# STM32MP25XXAK_Power.net
KiCad netlist of a schematic drawn in Altium Designer
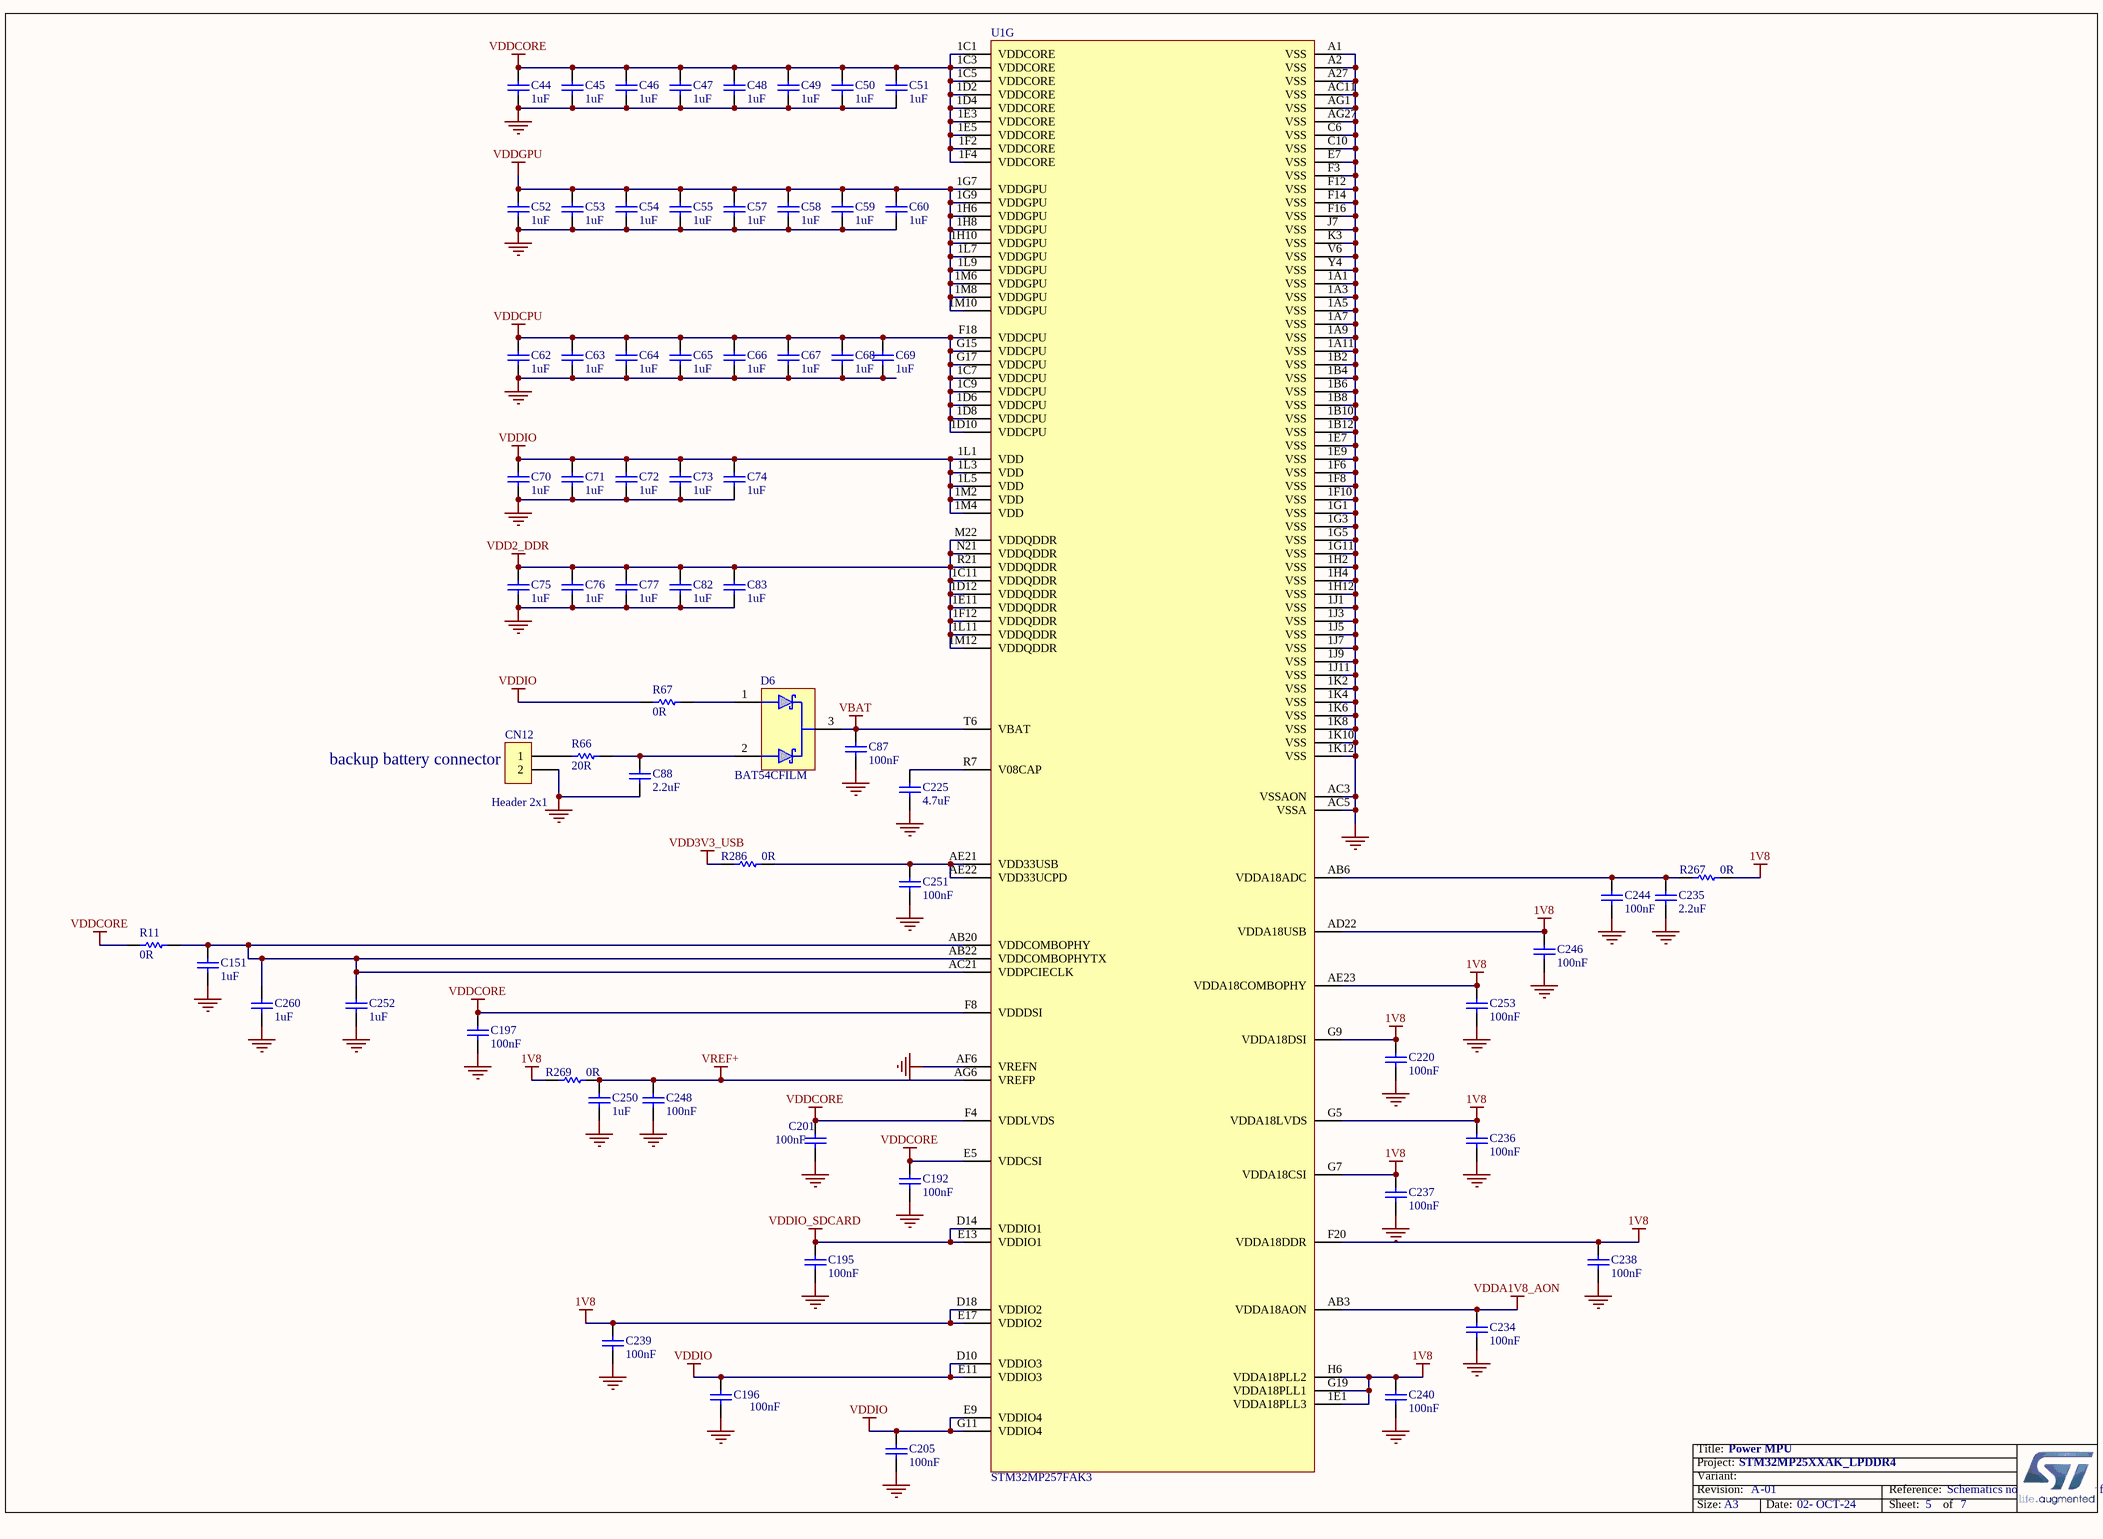
[diagram p0: STM32MP25XXAK Power.SchDoc]

(export (version "E")
  (design (tool "Eeschema 10.0.6"))
  (components
    (comp (ref "C44")
      (value "1uF")
      (footprint "C0201_MURATA_GRM033_H0P3")
      (description "Capacitor, MLCC, 1uF, 6.3V, X5R, +/-20%, 0201, T=0,3mm")
      (fields (field (name "INTERNAL_PART_NUMBER") "MCD-02377") (field (name "MANUFACTURER") "MURATA"))
      (libsource (lib "MCD_PARTS_database") (part "Capacitor"))
    )
    (comp (ref "C45")
      (value "1uF")
      (footprint "C0201_MURATA_GRM033_H0P3")
      (description "Capacitor, MLCC, 1uF, 6.3V, X5R, +/-20%, 0201, T=0,3mm")
      (fields (field (name "INTERNAL_PART_NUMBER") "MCD-02377") (field (name "MANUFACTURER") "MURATA"))
      (libsource (lib "MCD_PARTS_database") (part "Capacitor"))
    )
    (comp (ref "C46")
      (value "1uF")
      (footprint "C0201_MURATA_GRM033_H0P3")
      (description "Capacitor, MLCC, 1uF, 6.3V, X5R, +/-20%, 0201, T=0,3mm")
      (fields (field (name "INTERNAL_PART_NUMBER") "MCD-02377") (field (name "MANUFACTURER") "MURATA"))
      (libsource (lib "MCD_PARTS_database") (part "Capacitor"))
    )
    (comp (ref "C47")
      (value "1uF")
      (footprint "C0201_MURATA_GRM033_H0P3")
      (description "Capacitor, MLCC, 1uF, 6.3V, X5R, +/-20%, 0201, T=0,3mm")
      (fields (field (name "INTERNAL_PART_NUMBER") "MCD-02377") (field (name "MANUFACTURER") "MURATA"))
      (libsource (lib "MCD_PARTS_database") (part "Capacitor"))
    )
    (comp (ref "C48")
      (value "1uF")
      (footprint "C0201_MURATA_GRM033_H0P3")
      (description "Capacitor, MLCC, 1uF, 6.3V, X5R, +/-20%, 0201, T=0,3mm")
      (fields (field (name "INTERNAL_PART_NUMBER") "MCD-02377") (field (name "MANUFACTURER") "MURATA"))
      (libsource (lib "MCD_PARTS_database") (part "Capacitor"))
    )
    (comp (ref "C49")
      (value "1uF")
      (footprint "C0201_MURATA_GRM033_H0P3")
      (description "Capacitor, MLCC, 1uF, 6.3V, X5R, +/-20%, 0201, T=0,3mm")
      (fields (field (name "INTERNAL_PART_NUMBER") "MCD-02377") (field (name "MANUFACTURER") "MURATA"))
      (libsource (lib "MCD_PARTS_database") (part "Capacitor"))
    )
    (comp (ref "C50")
      (value "1uF")
      (footprint "C0201_MURATA_GRM033_H0P3")
      (description "Capacitor, MLCC, 1uF, 6.3V, X5R, +/-20%, 0201, T=0,3mm")
      (fields (field (name "INTERNAL_PART_NUMBER") "MCD-02377") (field (name "MANUFACTURER") "MURATA"))
      (libsource (lib "MCD_PARTS_database") (part "Capacitor"))
    )
    (comp (ref "C51")
      (value "1uF")
      (footprint "C0201_MURATA_GRM033_H0P3")
      (description "Capacitor, MLCC, 1uF, 6.3V, X5R, +/-20%, 0201, T=0,3mm")
      (fields (field (name "INTERNAL_PART_NUMBER") "MCD-02377") (field (name "MANUFACTURER") "MURATA"))
      (libsource (lib "MCD_PARTS_database") (part "Capacitor"))
    )
    (comp (ref "C52")
      (value "1uF")
      (footprint "C0201_MURATA_GRM033_H0P3")
      (description "Capacitor, MLCC, 1uF, 6.3V, X5R, +/-20%, 0201, T=0,3mm")
      (fields (field (name "INTERNAL_PART_NUMBER") "MCD-02377") (field (name "MANUFACTURER") "MURATA"))
      (libsource (lib "MCD_PARTS_database") (part "Capacitor"))
    )
    (comp (ref "C53")
      (value "1uF")
      (footprint "C0201_MURATA_GRM033_H0P3")
      (description "Capacitor, MLCC, 1uF, 6.3V, X5R, +/-20%, 0201, T=0,3mm")
      (fields (field (name "INTERNAL_PART_NUMBER") "MCD-02377") (field (name "MANUFACTURER") "MURATA"))
      (libsource (lib "MCD_PARTS_database") (part "Capacitor"))
    )
    (comp (ref "C54")
      (value "1uF")
      (footprint "C0201_MURATA_GRM033_H0P3")
      (description "Capacitor, MLCC, 1uF, 6.3V, X5R, +/-20%, 0201, T=0,3mm")
      (fields (field (name "INTERNAL_PART_NUMBER") "MCD-02377") (field (name "MANUFACTURER") "MURATA"))
      (libsource (lib "MCD_PARTS_database") (part "Capacitor"))
    )
    (comp (ref "C55")
      (value "1uF")
      (footprint "C0201_MURATA_GRM033_H0P3")
      (description "Capacitor, MLCC, 1uF, 6.3V, X5R, +/-20%, 0201, T=0,3mm")
      (fields (field (name "INTERNAL_PART_NUMBER") "MCD-02377") (field (name "MANUFACTURER") "MURATA"))
      (libsource (lib "MCD_PARTS_database") (part "Capacitor"))
    )
    (comp (ref "C57")
      (value "1uF")
      (footprint "C0201_MURATA_GRM033_H0P3")
      (description "Capacitor, MLCC, 1uF, 6.3V, X5R, +/-20%, 0201, T=0,3mm")
      (fields (field (name "INTERNAL_PART_NUMBER") "MCD-02377") (field (name "MANUFACTURER") "MURATA"))
      (libsource (lib "MCD_PARTS_database") (part "Capacitor"))
    )
    (comp (ref "C58")
      (value "1uF")
      (footprint "C0201_MURATA_GRM033_H0P3")
      (description "Capacitor, MLCC, 1uF, 6.3V, X5R, +/-20%, 0201, T=0,3mm")
      (fields (field (name "INTERNAL_PART_NUMBER") "MCD-02377") (field (name "MANUFACTURER") "MURATA"))
      (libsource (lib "MCD_PARTS_database") (part "Capacitor"))
    )
    (comp (ref "C59")
      (value "1uF")
      (footprint "C0201_MURATA_GRM033_H0P3")
      (description "Capacitor, MLCC, 1uF, 6.3V, X5R, +/-20%, 0201, T=0,3mm")
      (fields (field (name "INTERNAL_PART_NUMBER") "MCD-02377") (field (name "MANUFACTURER") "MURATA"))
      (libsource (lib "MCD_PARTS_database") (part "Capacitor"))
    )
    (comp (ref "C60")
      (value "1uF")
      (footprint "C0201_MURATA_GRM033_H0P3")
      (description "Capacitor, MLCC, 1uF, 6.3V, X5R, +/-20%, 0201, T=0,3mm")
      (fields (field (name "INTERNAL_PART_NUMBER") "MCD-02377") (field (name "MANUFACTURER") "MURATA"))
      (libsource (lib "MCD_PARTS_database") (part "Capacitor"))
    )
    (comp (ref "C62")
      (value "1uF")
      (footprint "C0201_MURATA_GRM033_H0P3")
      (description "Capacitor, MLCC, 1uF, 6.3V, X5R, +/-20%, 0201, T=0,3mm")
      (fields (field (name "INTERNAL_PART_NUMBER") "MCD-02377") (field (name "MANUFACTURER") "MURATA"))
      (libsource (lib "MCD_PARTS_database") (part "Capacitor"))
    )
    (comp (ref "C63")
      (value "1uF")
      (footprint "C0201_MURATA_GRM033_H0P3")
      (description "Capacitor, MLCC, 1uF, 6.3V, X5R, +/-20%, 0201, T=0,3mm")
      (fields (field (name "INTERNAL_PART_NUMBER") "MCD-02377") (field (name "MANUFACTURER") "MURATA"))
      (libsource (lib "MCD_PARTS_database") (part "Capacitor"))
    )
    (comp (ref "C64")
      (value "1uF")
      (footprint "C0201_MURATA_GRM033_H0P3")
      (description "Capacitor, MLCC, 1uF, 6.3V, X5R, +/-20%, 0201, T=0,3mm")
      (fields (field (name "INTERNAL_PART_NUMBER") "MCD-02377") (field (name "MANUFACTURER") "MURATA"))
      (libsource (lib "MCD_PARTS_database") (part "Capacitor"))
    )
    (comp (ref "C65")
      (value "1uF")
      (footprint "C0201_MURATA_GRM033_H0P3")
      (description "Capacitor, MLCC, 1uF, 6.3V, X5R, +/-20%, 0201, T=0,3mm")
      (fields (field (name "INTERNAL_PART_NUMBER") "MCD-02377") (field (name "MANUFACTURER") "MURATA"))
      (libsource (lib "MCD_PARTS_database") (part "Capacitor"))
    )
    (comp (ref "C66")
      (value "1uF")
      (footprint "C0201_MURATA_GRM033_H0P3")
      (description "Capacitor, MLCC, 1uF, 6.3V, X5R, +/-20%, 0201, T=0,3mm")
      (fields (field (name "INTERNAL_PART_NUMBER") "MCD-02377") (field (name "MANUFACTURER") "MURATA"))
      (libsource (lib "MCD_PARTS_database") (part "Capacitor"))
    )
    (comp (ref "C67")
      (value "1uF")
      (footprint "C0201_MURATA_GRM033_H0P3")
      (description "Capacitor, MLCC, 1uF, 6.3V, X5R, +/-20%, 0201, T=0,3mm")
      (fields (field (name "INTERNAL_PART_NUMBER") "MCD-02377") (field (name "MANUFACTURER") "MURATA"))
      (libsource (lib "MCD_PARTS_database") (part "Capacitor"))
    )
    (comp (ref "C68")
      (value "1uF")
      (footprint "C0201_MURATA_GRM033_H0P3")
      (description "Capacitor, MLCC, 1uF, 6.3V, X5R, +/-20%, 0201, T=0,3mm")
      (fields (field (name "INTERNAL_PART_NUMBER") "MCD-02377") (field (name "MANUFACTURER") "MURATA"))
      (libsource (lib "MCD_PARTS_database") (part "Capacitor"))
    )
    (comp (ref "C69")
      (value "1uF")
      (footprint "C0201_MURATA_GRM033_H0P3")
      (description "Capacitor, MLCC, 1uF, 6.3V, X5R, +/-20%, 0201, T=0,3mm")
      (fields (field (name "INTERNAL_PART_NUMBER") "MCD-02377") (field (name "MANUFACTURER") "MURATA"))
      (libsource (lib "MCD_PARTS_database") (part "Capacitor"))
    )
    (comp (ref "C70")
      (value "1uF")
      (footprint "C0201_MURATA_GRM033_H0P3")
      (description "Capacitor, MLCC, 1uF, 6.3V, X5R, +/-20%, 0201, T=0,3mm")
      (fields (field (name "INTERNAL_PART_NUMBER") "MCD-02377") (field (name "MANUFACTURER") "MURATA"))
      (libsource (lib "MCD_PARTS_database") (part "Capacitor"))
    )
    (comp (ref "C71")
      (value "1uF")
      (footprint "C0201_MURATA_GRM033_H0P3")
      (description "Capacitor, MLCC, 1uF, 6.3V, X5R, +/-20%, 0201, T=0,3mm")
      (fields (field (name "INTERNAL_PART_NUMBER") "MCD-02377") (field (name "MANUFACTURER") "MURATA"))
      (libsource (lib "MCD_PARTS_database") (part "Capacitor"))
    )
    (comp (ref "C72")
      (value "1uF")
      (footprint "C0201_MURATA_GRM033_H0P3")
      (description "Capacitor, MLCC, 1uF, 6.3V, X5R, +/-20%, 0201, T=0,3mm")
      (fields (field (name "INTERNAL_PART_NUMBER") "MCD-02377") (field (name "MANUFACTURER") "MURATA"))
      (libsource (lib "MCD_PARTS_database") (part "Capacitor"))
    )
    (comp (ref "C73")
      (value "1uF")
      (footprint "C0201_MURATA_GRM033_H0P3")
      (description "Capacitor, MLCC, 1uF, 6.3V, X5R, +/-20%, 0201, T=0,3mm")
      (fields (field (name "INTERNAL_PART_NUMBER") "MCD-02377") (field (name "MANUFACTURER") "MURATA"))
      (libsource (lib "MCD_PARTS_database") (part "Capacitor"))
    )
    (comp (ref "C74")
      (value "1uF")
      (footprint "C0201_MURATA_GRM033_H0P3")
      (description "Capacitor, MLCC, 1uF, 6.3V, X5R, +/-20%, 0201, T=0,3mm")
      (fields (field (name "INTERNAL_PART_NUMBER") "MCD-02377") (field (name "MANUFACTURER") "MURATA"))
      (libsource (lib "MCD_PARTS_database") (part "Capacitor"))
    )
    (comp (ref "C75")
      (value "1uF")
      (footprint "C0201_MURATA_GRM033_H0P3")
      (description "Capacitor, MLCC, 1uF, 6.3V, X5R, +/-20%, 0201, T=0,3mm")
      (fields (field (name "INTERNAL_PART_NUMBER") "MCD-02377") (field (name "MANUFACTURER") "MURATA"))
      (libsource (lib "MCD_PARTS_database") (part "Capacitor"))
    )
    (comp (ref "C76")
      (value "1uF")
      (footprint "C0201_MURATA_GRM033_H0P3")
      (description "Capacitor, MLCC, 1uF, 6.3V, X5R, +/-20%, 0201, T=0,3mm")
      (fields (field (name "INTERNAL_PART_NUMBER") "MCD-02377") (field (name "MANUFACTURER") "MURATA"))
      (libsource (lib "MCD_PARTS_database") (part "Capacitor"))
    )
    (comp (ref "C77")
      (value "1uF")
      (footprint "C0201_MURATA_GRM033_H0P3")
      (description "Capacitor, MLCC, 1uF, 6.3V, X5R, +/-20%, 0201, T=0,3mm")
      (fields (field (name "INTERNAL_PART_NUMBER") "MCD-02377") (field (name "MANUFACTURER") "MURATA"))
      (libsource (lib "MCD_PARTS_database") (part "Capacitor"))
    )
    (comp (ref "C82")
      (value "1uF")
      (footprint "C0201_MURATA_GRM033_H0P3")
      (description "Capacitor, MLCC, 1uF, 6.3V, X5R, +/-20%, 0201, T=0,3mm")
      (fields (field (name "INTERNAL_PART_NUMBER") "MCD-02377") (field (name "MANUFACTURER") "MURATA"))
      (libsource (lib "MCD_PARTS_database") (part "Capacitor"))
    )
    (comp (ref "C83")
      (value "1uF")
      (footprint "C0201_MURATA_GRM033_H0P3")
      (description "Capacitor, MLCC, 1uF, 6.3V, X5R, +/-20%, 0201, T=0,3mm")
      (fields (field (name "INTERNAL_PART_NUMBER") "MCD-02377") (field (name "MANUFACTURER") "MURATA"))
      (libsource (lib "MCD_PARTS_database") (part "Capacitor"))
    )
    (comp (ref "C87")
      (value "100nF")
      (footprint "C0402")
      (description "Capacitor,100nF,16V,X7R,10%,0402")
      (fields
        (field (name "INTERNAL_PART_NUMBER") "MCD-00006")
        (field (name "MANUFACTURER_PART_NUMBER") "CC0402KRX7R7BB104")
        (field (name "PROVIDED_BY") "SUBCO")
      )
      (libsource (lib "MCD_PARTS_database") (part "Capacitor"))
    )
    (comp (ref "C88")
      (value "2.2uF")
      (footprint "C0402")
      (description "Capacitor, MLCC, 2.2uF, 6V3, X5R,+/-10%, 0402, T=0.5mm")
      (fields (field (name "INTERNAL_PART_NUMBER") "MCD-01823") (field (name "MANUFACTURER") "MURATA"))
      (libsource (lib "MCD_PARTS_database") (part "Capacitor"))
    )
    (comp (ref "C151")
      (value "1uF")
      (footprint "C0201_MURATA_GRM033_H0P3")
      (description "Capacitor, MLCC, 1uF, 6.3V, X5R, +/-20%, 0201, T=0,3mm")
      (fields
        (field (name "INTERNAL_PART_NUMBER") "MCD-02377")
        (field (name "MANUFACTURER_PART_NUMBER") "GRM033R60J105MEA2")
      )
      (libsource (lib "MCD_PARTS_database") (part "Capacitor"))
    )
    (comp (ref "C192")
      (value "100nF")
      (footprint "C0201_MURATA_GRM033_H0P3")
      (description "Capacitor, MLCC,100nF, 10V, X7R, +/-10%, 0201, T=0.3mm")
      (fields (field (name "INTERNAL_PART_NUMBER") "MCD-01535") (field (name "MANUFACTURER") "MURATA"))
      (libsource (lib "MCD_PARTS_database") (part "Capacitor"))
    )
    (comp (ref "C195")
      (value "100nF")
      (footprint "C0201_MURATA_GRM033_H0P3")
      (description "Capacitor, MLCC,100nF, 10V, X7R, +/-10%, 0201, T=0.3mm")
      (fields (field (name "INTERNAL_PART_NUMBER") "MCD-01535") (field (name "MANUFACTURER") "MURATA"))
      (libsource (lib "MCD_PARTS_database") (part "Capacitor"))
    )
    (comp (ref "C196")
      (value "100nF")
      (footprint "C0201_MURATA_GRM033_H0P3")
      (description "Capacitor, MLCC,100nF, 10V, X7R, +/-10%, 0201, T=0.3mm")
      (fields (field (name "INTERNAL_PART_NUMBER") "MCD-01535") (field (name "MANUFACTURER") "MURATA"))
      (libsource (lib "MCD_PARTS_database") (part "Capacitor"))
    )
    (comp (ref "C197")
      (value "100nF")
      (footprint "C0201_MURATA_GRM033_H0P3")
      (description "Capacitor, MLCC,100nF, 10V, X7R, +/-10%, 0201, T=0.3mm")
      (fields (field (name "INTERNAL_PART_NUMBER") "MCD-01535") (field (name "MANUFACTURER") "MURATA"))
      (libsource (lib "MCD_PARTS_database") (part "Capacitor"))
    )
    (comp (ref "C201")
      (value "100nF")
      (footprint "C0201_MURATA_GRM033_H0P3")
      (description "Capacitor, MLCC,100nF, 10V, X7R, +/-10%, 0201, T=0.3mm")
      (fields (field (name "INTERNAL_PART_NUMBER") "MCD-01535") (field (name "MANUFACTURER") "MURATA"))
      (libsource (lib "MCD_PARTS_database") (part "Capacitor"))
    )
    (comp (ref "C205")
      (value "100nF")
      (footprint "C0201_MURATA_GRM033_H0P3")
      (description "Capacitor, MLCC,100nF, 10V, X7R, +/-10%, 0201, T=0.3mm")
      (fields (field (name "INTERNAL_PART_NUMBER") "MCD-01535") (field (name "MANUFACTURER") "MURATA"))
      (libsource (lib "MCD_PARTS_database") (part "Capacitor"))
    )
    (comp (ref "C220")
      (value "100nF")
      (footprint "C0201_MURATA_GRM033_H0P3")
      (description "Capacitor, MLCC,100nF, 10V, X7R, +/-10%, 0201, T=0.3mm")
      (fields (field (name "INTERNAL_PART_NUMBER") "MCD-01535") (field (name "MANUFACTURER") "MURATA"))
      (libsource (lib "MCD_PARTS_database") (part "Capacitor"))
    )
    (comp (ref "C225")
      (value "4.7uF")
      (footprint "C0201_H0P5")
      (description "Capacitor, MLCC, 4,7uF, 6V3, X5R, +/-20%, 0201, T=0.5mm")
      (fields (field (name "INTERNAL_PART_NUMBER") "MCD-01534") (field (name "MANUFACTURER") "MURATA"))
      (libsource (lib "MCD_PARTS_database") (part "Capacitor"))
    )
    (comp (ref "C234")
      (value "100nF")
      (footprint "C0201_MURATA_GRM033_H0P3")
      (description "Capacitor, MLCC,100nF, 10V, X7R, +/-10%, 0201, T=0.3mm")
      (fields (field (name "INTERNAL_PART_NUMBER") "MCD-01535") (field (name "MANUFACTURER") "MURATA"))
      (libsource (lib "MCD_PARTS_database") (part "Capacitor"))
    )
    (comp (ref "C235")
      (value "2.2uF")
      (footprint "C0201_H0P5")
      (description "Capacitor, MLCC, 2.2uF, 10V, X5R,+/-10%, 0201, T=0.5mm")
      (fields (field (name "INTERNAL_PART_NUMBER") "MCD-02235") (field (name "MANUFACTURER") "MURATA"))
      (libsource (lib "MCD_PARTS_database") (part "Capacitor"))
    )
    (comp (ref "C236")
      (value "100nF")
      (footprint "C0201_MURATA_GRM033_H0P3")
      (description "Capacitor, MLCC,100nF, 10V, X7R, +/-10%, 0201, T=0.3mm")
      (fields (field (name "INTERNAL_PART_NUMBER") "MCD-01535") (field (name "MANUFACTURER") "MURATA"))
      (libsource (lib "MCD_PARTS_database") (part "Capacitor"))
    )
    (comp (ref "C237")
      (value "100nF")
      (footprint "C0201_MURATA_GRM033_H0P3")
      (description "Capacitor, MLCC,100nF, 10V, X7R, +/-10%, 0201, T=0.3mm")
      (fields (field (name "INTERNAL_PART_NUMBER") "MCD-01535") (field (name "MANUFACTURER") "MURATA"))
      (libsource (lib "MCD_PARTS_database") (part "Capacitor"))
    )
    (comp (ref "C238")
      (value "100nF")
      (footprint "C0201_MURATA_GRM033_H0P3")
      (description "Capacitor, MLCC,100nF, 10V, X7R, +/-10%, 0201, T=0.3mm")
      (fields (field (name "INTERNAL_PART_NUMBER") "MCD-01535") (field (name "MANUFACTURER") "MURATA"))
      (libsource (lib "MCD_PARTS_database") (part "Capacitor"))
    )
    (comp (ref "C239")
      (value "100nF")
      (footprint "C0201_MURATA_GRM033_H0P3")
      (description "Capacitor, MLCC,100nF, 10V, X7R, +/-10%, 0201, T=0.3mm")
      (fields (field (name "INTERNAL_PART_NUMBER") "MCD-01535") (field (name "MANUFACTURER") "MURATA"))
      (libsource (lib "MCD_PARTS_database") (part "Capacitor"))
    )
    (comp (ref "C240")
      (value "100nF")
      (footprint "C0201_MURATA_GRM033_H0P3")
      (description "Capacitor, MLCC,100nF, 10V, X7R, +/-10%, 0201, T=0.3mm")
      (fields (field (name "INTERNAL_PART_NUMBER") "MCD-01535") (field (name "MANUFACTURER") "MURATA"))
      (libsource (lib "MCD_PARTS_database") (part "Capacitor"))
    )
    (comp (ref "C244")
      (value "100nF")
      (footprint "C0201_MURATA_GRM033_H0P3")
      (description "Capacitor, MLCC,100nF, 10V, X7R, +/-10%, 0201, T=0.3mm")
      (fields (field (name "INTERNAL_PART_NUMBER") "MCD-01535") (field (name "MANUFACTURER") "MURATA"))
      (libsource (lib "MCD_PARTS_database") (part "Capacitor"))
    )
    (comp (ref "C246")
      (value "100nF")
      (footprint "C0201_MURATA_GRM033_H0P3")
      (description "Capacitor, MLCC,100nF, 10V, X7R, +/-10%, 0201, T=0.3mm")
      (fields (field (name "INTERNAL_PART_NUMBER") "MCD-01535") (field (name "MANUFACTURER") "MURATA"))
      (libsource (lib "MCD_PARTS_database") (part "Capacitor"))
    )
    (comp (ref "C248")
      (value "100nF")
      (footprint "C0201_MURATA_GRM033_H0P3")
      (description "Capacitor, MLCC,100nF, 10V, X7R, +/-10%, 0201, T=0.3mm")
      (fields (field (name "INTERNAL_PART_NUMBER") "MCD-01535") (field (name "MANUFACTURER") "MURATA"))
      (libsource (lib "MCD_PARTS_database") (part "Capacitor"))
    )
    (comp (ref "C250")
      (value "1uF")
      (footprint "C0201_MURATA_GRM033_H0P3")
      (description "Capacitor, MLCC, 1uF, 6.3V, X5R, +/-20%, 0201, T=0,3mm")
      (fields
        (field (name "INTERNAL_PART_NUMBER") "MCD-02377")
        (field (name "MANUFACTURER_PART_NUMBER") "GRM033R60J105MEA2")
      )
      (libsource (lib "MCD_PARTS_database") (part "Capacitor"))
    )
    (comp (ref "C251")
      (value "100nF")
      (footprint "C0201_MURATA_GRM033_H0P3")
      (description "Capacitor, MLCC,100nF, 10V, X7R, +/-10%, 0201, T=0.3mm")
      (fields (field (name "INTERNAL_PART_NUMBER") "MCD-01535") (field (name "MANUFACTURER") "MURATA"))
      (libsource (lib "MCD_PARTS_database") (part "Capacitor"))
    )
    (comp (ref "C252")
      (value "1uF")
      (footprint "C0201_MURATA_GRM033_H0P3")
      (description "Capacitor, MLCC, 1uF, 6.3V, X5R, +/-20%, 0201, T=0,3mm")
      (fields
        (field (name "INTERNAL_PART_NUMBER") "MCD-02377")
        (field (name "MANUFACTURER_PART_NUMBER") "GRM033R60J105MEA2")
      )
      (libsource (lib "MCD_PARTS_database") (part "Capacitor"))
    )
    (comp (ref "C253")
      (value "100nF")
      (footprint "C0201_MURATA_GRM033_H0P3")
      (description "Capacitor, MLCC,100nF, 10V, X7R, +/-10%, 0201, T=0.3mm")
      (fields (field (name "INTERNAL_PART_NUMBER") "MCD-01535") (field (name "MANUFACTURER") "MURATA"))
      (libsource (lib "MCD_PARTS_database") (part "Capacitor"))
    )
    (comp (ref "C260")
      (value "1uF")
      (footprint "C0201_MURATA_GRM033_H0P3")
      (description "Capacitor, MLCC, 1uF, 6.3V, X5R, +/-20%, 0201, T=0,3mm")
      (fields
        (field (name "INTERNAL_PART_NUMBER") "MCD-02377")
        (field (name "MANUFACTURER_PART_NUMBER") "GRM033R60J105MEA2")
      )
      (libsource (lib "MCD_PARTS_database") (part "Capacitor"))
    )
    (comp (ref "CN12")
      (value "Header 2x1")
      (footprint "CON_MOLEX_53047-0210")
      (description "Header 2 circuits, 1.25mm Pitch ,  Vertical, with Friction Lock")
      (fields
        (field (name "INTERNAL_PART_NUMBER") "MCD-00655")
        (field (name "MANUFACTURER_PART_NUMBER") "53047-0210")
        (field (name "PROVIDED_BY") "SUBCO")
      )
      (libsource (lib "MCD_PARTS_database") (part "Header 2x1"))
    )
    (comp (ref "D6")
      (value "BAT54CFILM")
      (footprint "DIO_SOT23")
      (description "Diode, Schottky, Dual Common Cathode, 0V3, 300mA, 40V, SOT-23")
      (fields
        (field (name "INTERNAL_PART_NUMBER") "MCD-03280")
        (field (name "MANUFACTURER") "STMICROELECTRONICS")
      )
      (libsource (lib "MCD_PARTS_database") (part "DIODE_3P_DUAL_COMMON_CATHODE"))
    )
    (comp (ref "R11")
      (value "0R")
      (footprint "R0603")
      (description "Resistor, 0R, 0603, +/-5%, 1/10W")
      (fields (field (name "INTERNAL_PART_NUMBER") "MCD-00056") (field (name "MANUFACTURER") "YAGEO"))
      (libsource (lib "MCD_PARTS_database") (part "Resistor"))
    )
    (comp (ref "R66")
      (value "20R")
      (footprint "R0402")
      (description "Resistor, 20R, 0402, +/-1%, 1/16W")
      (fields (field (name "INTERNAL_PART_NUMBER") "MCD-00058") (field (name "BMS_PART_NUMBER") "9131027"))
      (libsource (lib "MCD_PARTS_database") (part "Resistor"))
    )
    (comp (ref "R67")
      (value "0R")
      (footprint "R0402")
      (description "Resistor, 0R, 0402, +/-5%, 1/16W")
      (fields
        (field (name "INTERNAL_PART_NUMBER") "MCD-00052")
        (field (name "MANUFACTURER_PART_NUMBER") "RC0402JR-070RL")
      )
      (libsource (lib "MCD_PARTS_database") (part "Resistor"))
    )
    (comp (ref "R267")
      (value "0R")
      (footprint "R0402")
      (description "Resistor,0R,0402,5%,1/16W")
      (fields
        (field (name "INTERNAL_PART_NUMBER") "MCD-00052")
        (field (name "MANUFACTURER_PART_NUMBER") "RC0402JR-070RL")
        (field (name "PROVIDED_BY") "SUBCO")
      )
      (libsource (lib "MCD_PARTS_database") (part "Resistor"))
    )
    (comp (ref "R269")
      (value "0R")
      (footprint "R0402")
      (description "Resistor,0R,0402,5%,1/16W")
      (fields
        (field (name "INTERNAL_PART_NUMBER") "MCD-00052")
        (field (name "MANUFACTURER_PART_NUMBER") "RC0402JR-070RL")
        (field (name "PROVIDED_BY") "SUBCO")
      )
      (libsource (lib "MCD_PARTS_database") (part "Resistor"))
    )
    (comp (ref "R286")
      (value "0R")
      (footprint "R0402")
      (description "Resistor,0R,0402,5%,1/16W")
      (fields
        (field (name "INTERNAL_PART_NUMBER") "MCD-00052")
        (field (name "MANUFACTURER_PART_NUMBER") "RC0402JR-070RL")
        (field (name "PROVIDED_BY") "SUBCO")
      )
      (libsource (lib "MCD_PARTS_database") (part "Resistor"))
    )
    (comp (ref "U1")
      (value "STM32MP257FAK3")
      (footprint "ICC_TFBGA424_14X14_P050_H1P20_CODE-B0A2")
      (description "MPU , 2xCortex-A35@1.5GHz, Cortex-M33@400MHz, TFBGA 14x14, pitch 0.5, 808 KB SRAM, With Crypto")
      (fields
        (field (name "INTERNAL_PART_NUMBER") "MCD-03375")
        (field (name "MANUFACTURER") "STMICROELECTRONICS")
      )
      (libsource (lib "MCD_PARTS_database") (part "STM32MP257FAK3"))
    )
  )
  (nets
    (net (code "1") (name "1V8") (class "Default")
      (node (ref "C220") (pin "2") (pinfunction "2_2") (pintype "passive"))
      (node (ref "C236") (pin "2") (pinfunction "2_2") (pintype "passive"))
      (node (ref "C237") (pin "2") (pinfunction "2_2") (pintype "passive"))
      (node (ref "C238") (pin "2") (pinfunction "2_2") (pintype "passive"))
      (node (ref "C239") (pin "2") (pinfunction "2_2") (pintype "passive"))
      (node (ref "C240") (pin "2") (pinfunction "2_2") (pintype "passive"))
      (node (ref "C246") (pin "2") (pinfunction "2_2") (pintype "passive"))
      (node (ref "C253") (pin "2") (pinfunction "2_2") (pintype "passive"))
      (node (ref "R267") (pin "2") (pinfunction "2_2") (pintype "passive"))
      (node (ref "R269") (pin "1") (pinfunction "1_1") (pintype "passive"))
      (node (ref "U1") (pin "1E1") (pinfunction "VDDA18PLL3_1E1") (pintype "passive"))
      (node (ref "U1") (pin "AD22") (pinfunction "VDDA18USB_AD22") (pintype "passive"))
      (node (ref "U1") (pin "AE23") (pinfunction "VDDA18COMBOPHY_AE23") (pintype "passive"))
      (node (ref "U1") (pin "D18") (pinfunction "VDDIO2_D18") (pintype "passive"))
      (node (ref "U1") (pin "E17") (pinfunction "VDDIO2_E17") (pintype "passive"))
      (node (ref "U1") (pin "F20") (pinfunction "VDDA18DDR_F20") (pintype "passive"))
      (node (ref "U1") (pin "G19") (pinfunction "VDDA18PLL1_G19") (pintype "passive"))
      (node (ref "U1") (pin "G5") (pinfunction "VDDA18LVDS_G5") (pintype "passive"))
      (node (ref "U1") (pin "G7") (pinfunction "VDDA18CSI_G7") (pintype "passive"))
      (node (ref "U1") (pin "G9") (pinfunction "VDDA18DSI_G9") (pintype "passive"))
      (node (ref "U1") (pin "H6") (pinfunction "VDDA18PLL2_H6") (pintype "passive"))
    )
    (net (code "2") (name "GND") (class "Default")
      (node (ref "C151") (pin "1") (pinfunction "1_1") (pintype "passive"))
      (node (ref "C192") (pin "1") (pinfunction "1_1") (pintype "passive"))
      (node (ref "C195") (pin "1") (pinfunction "1_1") (pintype "passive"))
      (node (ref "C196") (pin "1") (pinfunction "1_1") (pintype "passive"))
      (node (ref "C197") (pin "1") (pinfunction "1_1") (pintype "passive"))
      (node (ref "C201") (pin "1") (pinfunction "1_1") (pintype "passive"))
      (node (ref "C205") (pin "1") (pinfunction "1_1") (pintype "passive"))
      (node (ref "C220") (pin "1") (pinfunction "1_1") (pintype "passive"))
      (node (ref "C225") (pin "1") (pinfunction "1_1") (pintype "passive"))
      (node (ref "C234") (pin "1") (pinfunction "1_1") (pintype "passive"))
      (node (ref "C235") (pin "1") (pinfunction "1_1") (pintype "passive"))
      (node (ref "C236") (pin "1") (pinfunction "1_1") (pintype "passive"))
      (node (ref "C237") (pin "1") (pinfunction "1_1") (pintype "passive"))
      (node (ref "C238") (pin "1") (pinfunction "1_1") (pintype "passive"))
      (node (ref "C239") (pin "1") (pinfunction "1_1") (pintype "passive"))
      (node (ref "C240") (pin "1") (pinfunction "1_1") (pintype "passive"))
      (node (ref "C244") (pin "1") (pinfunction "1_1") (pintype "passive"))
      (node (ref "C246") (pin "1") (pinfunction "1_1") (pintype "passive"))
      (node (ref "C248") (pin "1") (pinfunction "1_1") (pintype "passive"))
      (node (ref "C250") (pin "1") (pinfunction "1_1") (pintype "passive"))
      (node (ref "C251") (pin "1") (pinfunction "1_1") (pintype "passive"))
      (node (ref "C252") (pin "1") (pinfunction "1_1") (pintype "passive"))
      (node (ref "C253") (pin "1") (pinfunction "1_1") (pintype "passive"))
      (node (ref "C260") (pin "1") (pinfunction "1_1") (pintype "passive"))
      (node (ref "C44") (pin "2") (pinfunction "2_2") (pintype "passive"))
      (node (ref "C45") (pin "1") (pinfunction "1_1") (pintype "passive"))
      (node (ref "C46") (pin "1") (pinfunction "1_1") (pintype "passive"))
      (node (ref "C47") (pin "2") (pinfunction "2_2") (pintype "passive"))
      (node (ref "C48") (pin "1") (pinfunction "1_1") (pintype "passive"))
      (node (ref "C49") (pin "1") (pinfunction "1_1") (pintype "passive"))
      (node (ref "C50") (pin "1") (pinfunction "1_1") (pintype "passive"))
      (node (ref "C51") (pin "1") (pinfunction "1_1") (pintype "passive"))
      (node (ref "C52") (pin "1") (pinfunction "1_1") (pintype "passive"))
      (node (ref "C53") (pin "1") (pinfunction "1_1") (pintype "passive"))
      (node (ref "C54") (pin "1") (pinfunction "1_1") (pintype "passive"))
      (node (ref "C55") (pin "1") (pinfunction "1_1") (pintype "passive"))
      (node (ref "C57") (pin "1") (pinfunction "1_1") (pintype "passive"))
      (node (ref "C58") (pin "1") (pinfunction "1_1") (pintype "passive"))
      (node (ref "C59") (pin "1") (pinfunction "1_1") (pintype "passive"))
      (node (ref "C60") (pin "1") (pinfunction "1_1") (pintype "passive"))
      (node (ref "C62") (pin "2") (pinfunction "2_2") (pintype "passive"))
      (node (ref "C63") (pin "1") (pinfunction "1_1") (pintype "passive"))
      (node (ref "C64") (pin "1") (pinfunction "1_1") (pintype "passive"))
      (node (ref "C65") (pin "2") (pinfunction "2_2") (pintype "passive"))
      (node (ref "C66") (pin "1") (pinfunction "1_1") (pintype "passive"))
      (node (ref "C67") (pin "1") (pinfunction "1_1") (pintype "passive"))
      (node (ref "C68") (pin "1") (pinfunction "1_1") (pintype "passive"))
      (node (ref "C69") (pin "1") (pinfunction "1_1") (pintype "passive"))
      (node (ref "C70") (pin "2") (pinfunction "2_2") (pintype "passive"))
      (node (ref "C71") (pin "1") (pinfunction "1_1") (pintype "passive"))
      (node (ref "C72") (pin "1") (pinfunction "1_1") (pintype "passive"))
      (node (ref "C73") (pin "2") (pinfunction "2_2") (pintype "passive"))
      (node (ref "C74") (pin "1") (pinfunction "1_1") (pintype "passive"))
      (node (ref "C75") (pin "1") (pinfunction "1_1") (pintype "passive"))
      (node (ref "C76") (pin "1") (pinfunction "1_1") (pintype "passive"))
      (node (ref "C77") (pin "2") (pinfunction "2_2") (pintype "passive"))
      (node (ref "C82") (pin "1") (pinfunction "1_1") (pintype "passive"))
      (node (ref "C83") (pin "1") (pinfunction "1_1") (pintype "passive"))
      (node (ref "C87") (pin "1") (pinfunction "1_1") (pintype "passive"))
      (node (ref "C88") (pin "1") (pinfunction "1_1") (pintype "passive"))
      (node (ref "CN12") (pin "2") (pinfunction "2_2") (pintype "passive"))
      (node (ref "U1") (pin "1A1") (pinfunction "VSS_1A1") (pintype "passive"))
      (node (ref "U1") (pin "1A11") (pinfunction "VSS_1A11") (pintype "passive"))
      (node (ref "U1") (pin "1A3") (pinfunction "VSS_1A3") (pintype "passive"))
      (node (ref "U1") (pin "1A5") (pinfunction "VSS_1A5") (pintype "passive"))
      (node (ref "U1") (pin "1A7") (pinfunction "VSS_1A7") (pintype "passive"))
      (node (ref "U1") (pin "1A9") (pinfunction "VSS_1A9") (pintype "passive"))
      (node (ref "U1") (pin "1B10") (pinfunction "VSS_1B10") (pintype "passive"))
      (node (ref "U1") (pin "1B12") (pinfunction "VSS_1B12") (pintype "passive"))
      (node (ref "U1") (pin "1B2") (pinfunction "VSS_1B2") (pintype "passive"))
      (node (ref "U1") (pin "1B4") (pinfunction "VSS_1B4") (pintype "passive"))
      (node (ref "U1") (pin "1B6") (pinfunction "VSS_1B6") (pintype "passive"))
      (node (ref "U1") (pin "1B8") (pinfunction "VSS_1B8") (pintype "passive"))
      (node (ref "U1") (pin "1E7") (pinfunction "VSS_1E7") (pintype "passive"))
      (node (ref "U1") (pin "1E9") (pinfunction "VSS_1E9") (pintype "passive"))
      (node (ref "U1") (pin "1F10") (pinfunction "VSS_1F10") (pintype "passive"))
      (node (ref "U1") (pin "1F6") (pinfunction "VSS_1F6") (pintype "passive"))
      (node (ref "U1") (pin "1F8") (pinfunction "VSS_1F8") (pintype "passive"))
      (node (ref "U1") (pin "1G1") (pinfunction "VSS_1G1") (pintype "passive"))
      (node (ref "U1") (pin "1G11") (pinfunction "VSS_1G11") (pintype "passive"))
      (node (ref "U1") (pin "1G3") (pinfunction "VSS_1G3") (pintype "passive"))
      (node (ref "U1") (pin "1G5") (pinfunction "VSS_1G5") (pintype "passive"))
      (node (ref "U1") (pin "1H12") (pinfunction "VSS_1H12") (pintype "passive"))
      (node (ref "U1") (pin "1H2") (pinfunction "VSS_1H2") (pintype "passive"))
      (node (ref "U1") (pin "1H4") (pinfunction "VSS_1H4") (pintype "passive"))
      (node (ref "U1") (pin "1J1") (pinfunction "VSS_1J1") (pintype "passive"))
      (node (ref "U1") (pin "1J11") (pinfunction "VSS_1J11") (pintype "passive"))
      (node (ref "U1") (pin "1J3") (pinfunction "VSS_1J3") (pintype "passive"))
      (node (ref "U1") (pin "1J5") (pinfunction "VSS_1J5") (pintype "passive"))
      (node (ref "U1") (pin "1J7") (pinfunction "VSS_1J7") (pintype "passive"))
      (node (ref "U1") (pin "1J9") (pinfunction "VSS_1J9") (pintype "passive"))
      (node (ref "U1") (pin "1K10") (pinfunction "VSS_1K10") (pintype "passive"))
      (node (ref "U1") (pin "1K12") (pinfunction "VSS_1K12") (pintype "passive"))
      (node (ref "U1") (pin "1K2") (pinfunction "VSS_1K2") (pintype "passive"))
      (node (ref "U1") (pin "1K4") (pinfunction "VSS_1K4") (pintype "passive"))
      (node (ref "U1") (pin "1K6") (pinfunction "VSS_1K6") (pintype "passive"))
      (node (ref "U1") (pin "1K8") (pinfunction "VSS_1K8") (pintype "passive"))
      (node (ref "U1") (pin "A1") (pinfunction "VSS_A1") (pintype "passive"))
      (node (ref "U1") (pin "A2") (pinfunction "VSS_A2") (pintype "passive"))
      (node (ref "U1") (pin "A27") (pinfunction "VSS_A27") (pintype "passive"))
      (node (ref "U1") (pin "AC11") (pinfunction "VSS_AC11") (pintype "passive"))
      (node (ref "U1") (pin "AC3") (pinfunction "VSSAON_AC3") (pintype "passive"))
      (node (ref "U1") (pin "AC5") (pinfunction "VSSA_AC5") (pintype "passive"))
      (node (ref "U1") (pin "AF6") (pinfunction "VREFN_AF6") (pintype "passive"))
      (node (ref "U1") (pin "AG1") (pinfunction "VSS_AG1") (pintype "passive"))
      (node (ref "U1") (pin "AG27") (pinfunction "VSS_AG27") (pintype "passive"))
      (node (ref "U1") (pin "C10") (pinfunction "VSS_C10") (pintype "passive"))
      (node (ref "U1") (pin "C6") (pinfunction "VSS_C6") (pintype "passive"))
      (node (ref "U1") (pin "E7") (pinfunction "VSS_E7") (pintype "passive"))
      (node (ref "U1") (pin "F12") (pinfunction "VSS_F12") (pintype "passive"))
      (node (ref "U1") (pin "F14") (pinfunction "VSS_F14") (pintype "passive"))
      (node (ref "U1") (pin "F16") (pinfunction "VSS_F16") (pintype "passive"))
      (node (ref "U1") (pin "F3") (pinfunction "VSS_F3") (pintype "passive"))
      (node (ref "U1") (pin "J7") (pinfunction "VSS_J7") (pintype "passive"))
      (node (ref "U1") (pin "K3") (pinfunction "VSS_K3") (pintype "passive"))
      (node (ref "U1") (pin "V6") (pinfunction "VSS_V6") (pintype "passive"))
      (node (ref "U1") (pin "Y4") (pinfunction "VSS_Y4") (pintype "passive"))
    )
    (net (code "3") (name "Net-(C88-Pad2)") (class "Default")
      (node (ref "C88") (pin "2") (pinfunction "2_2") (pintype "passive"))
      (node (ref "D6") (pin "2") (pinfunction "2_2") (pintype "passive"))
      (node (ref "R66") (pin "2") (pinfunction "2_2") (pintype "passive"))
    )
    (net (code "4") (name "Net-(CN12-Pad1)") (class "Default")
      (node (ref "CN12") (pin "1") (pinfunction "1_1") (pintype "passive"))
      (node (ref "R66") (pin "1") (pinfunction "1_1") (pintype "passive"))
    )
    (net (code "5") (name "Net-(D6-Pad1)") (class "Default")
      (node (ref "D6") (pin "1") (pinfunction "1_1") (pintype "passive"))
      (node (ref "R67") (pin "1") (pinfunction "1_1") (pintype "passive"))
    )
    (net (code "6") (name "Net-(U1G-V08CAP)") (class "Default")
      (node (ref "C225") (pin "2") (pinfunction "2_2") (pintype "passive"))
      (node (ref "U1") (pin "R7") (pinfunction "V08CAP_R7") (pintype "passive"))
    )
    (net (code "7") (name "Net-(U1G-VDD33UCPD)") (class "Default")
      (node (ref "C251") (pin "2") (pinfunction "2_2") (pintype "passive"))
      (node (ref "R286") (pin "2") (pinfunction "2_2") (pintype "passive"))
      (node (ref "U1") (pin "AE21") (pinfunction "VDD33USB_AE21") (pintype "passive"))
      (node (ref "U1") (pin "AE22") (pinfunction "VDD33UCPD_AE22") (pintype "passive"))
    )
    (net (code "8") (name "Net-(U1G-VDDA18ADC)") (class "Default")
      (node (ref "C235") (pin "2") (pinfunction "2_2") (pintype "passive"))
      (node (ref "C244") (pin "2") (pinfunction "2_2") (pintype "passive"))
      (node (ref "R267") (pin "1") (pinfunction "1_1") (pintype "passive"))
      (node (ref "U1") (pin "AB6") (pinfunction "VDDA18ADC_AB6") (pintype "passive"))
    )
    (net (code "9") (name "Net-(U1G-VDDCOMBOPHY)") (class "Default")
      (node (ref "C151") (pin "2") (pinfunction "2_2") (pintype "passive"))
      (node (ref "C252") (pin "2") (pinfunction "2_2") (pintype "passive"))
      (node (ref "C260") (pin "2") (pinfunction "2_2") (pintype "passive"))
      (node (ref "R11") (pin "2") (pinfunction "2_2") (pintype "passive"))
      (node (ref "U1") (pin "AB20") (pinfunction "VDDCOMBOPHY_AB20") (pintype "passive"))
      (node (ref "U1") (pin "AB22") (pinfunction "VDDCOMBOPHYTX_AB22") (pintype "passive"))
      (node (ref "U1") (pin "AC21") (pinfunction "VDDPCIECLK_AC21") (pintype "passive"))
    )
    (net (code "10") (name "VBAT") (class "Default")
      (node (ref "C87") (pin "2") (pinfunction "2_2") (pintype "passive"))
      (node (ref "D6") (pin "3") (pinfunction "3_3") (pintype "passive"))
      (node (ref "U1") (pin "T6") (pinfunction "VBAT_T6") (pintype "passive"))
    )
    (net (code "11") (name "VDD2_DDR") (class "Default")
      (node (ref "C75") (pin "2") (pinfunction "2_2") (pintype "passive"))
      (node (ref "C76") (pin "2") (pinfunction "2_2") (pintype "passive"))
      (node (ref "C77") (pin "1") (pinfunction "1_1") (pintype "passive"))
      (node (ref "C82") (pin "2") (pinfunction "2_2") (pintype "passive"))
      (node (ref "C83") (pin "2") (pinfunction "2_2") (pintype "passive"))
      (node (ref "U1") (pin "1C11") (pinfunction "VDDQDDR_1C11") (pintype "passive"))
      (node (ref "U1") (pin "1D12") (pinfunction "VDDQDDR_1D12") (pintype "passive"))
      (node (ref "U1") (pin "1E11") (pinfunction "VDDQDDR_1E11") (pintype "passive"))
      (node (ref "U1") (pin "1F12") (pinfunction "VDDQDDR_1F12") (pintype "passive"))
      (node (ref "U1") (pin "1L11") (pinfunction "VDDQDDR_1L11") (pintype "passive"))
      (node (ref "U1") (pin "1M12") (pinfunction "VDDQDDR_1M12") (pintype "passive"))
      (node (ref "U1") (pin "M22") (pinfunction "VDDQDDR_M22") (pintype "passive"))
      (node (ref "U1") (pin "N21") (pinfunction "VDDQDDR_N21") (pintype "passive"))
      (node (ref "U1") (pin "R21") (pinfunction "VDDQDDR_R21") (pintype "passive"))
    )
    (net (code "12") (name "VDD3V3_USB") (class "Default")
      (node (ref "R286") (pin "1") (pinfunction "1_1") (pintype "passive"))
    )
    (net (code "13") (name "VDDA1V8_AON") (class "Default")
      (node (ref "C234") (pin "2") (pinfunction "2_2") (pintype "passive"))
      (node (ref "U1") (pin "AB3") (pinfunction "VDDA18AON_AB3") (pintype "passive"))
    )
    (net (code "14") (name "VDDCORE") (class "Default")
      (node (ref "C192") (pin "2") (pinfunction "2_2") (pintype "passive"))
      (node (ref "C197") (pin "2") (pinfunction "2_2") (pintype "passive"))
      (node (ref "C201") (pin "2") (pinfunction "2_2") (pintype "passive"))
      (node (ref "C44") (pin "1") (pinfunction "1_1") (pintype "passive"))
      (node (ref "C45") (pin "2") (pinfunction "2_2") (pintype "passive"))
      (node (ref "C46") (pin "2") (pinfunction "2_2") (pintype "passive"))
      (node (ref "C47") (pin "1") (pinfunction "1_1") (pintype "passive"))
      (node (ref "C48") (pin "2") (pinfunction "2_2") (pintype "passive"))
      (node (ref "C49") (pin "2") (pinfunction "2_2") (pintype "passive"))
      (node (ref "C50") (pin "2") (pinfunction "2_2") (pintype "passive"))
      (node (ref "C51") (pin "2") (pinfunction "2_2") (pintype "passive"))
      (node (ref "R11") (pin "1") (pinfunction "1_1") (pintype "passive"))
      (node (ref "U1") (pin "1C1") (pinfunction "VDDCORE_1C1") (pintype "passive"))
      (node (ref "U1") (pin "1C3") (pinfunction "VDDCORE_1C3") (pintype "passive"))
      (node (ref "U1") (pin "1C5") (pinfunction "VDDCORE_1C5") (pintype "passive"))
      (node (ref "U1") (pin "1D2") (pinfunction "VDDCORE_1D2") (pintype "passive"))
      (node (ref "U1") (pin "1D4") (pinfunction "VDDCORE_1D4") (pintype "passive"))
      (node (ref "U1") (pin "1E3") (pinfunction "VDDCORE_1E3") (pintype "passive"))
      (node (ref "U1") (pin "1E5") (pinfunction "VDDCORE_1E5") (pintype "passive"))
      (node (ref "U1") (pin "1F2") (pinfunction "VDDCORE_1F2") (pintype "passive"))
      (node (ref "U1") (pin "1F4") (pinfunction "VDDCORE_1F4") (pintype "passive"))
      (node (ref "U1") (pin "E5") (pinfunction "VDDCSI_E5") (pintype "passive"))
      (node (ref "U1") (pin "F4") (pinfunction "VDDLVDS_F4") (pintype "passive"))
      (node (ref "U1") (pin "F8") (pinfunction "VDDDSI_F8") (pintype "passive"))
    )
    (net (code "15") (name "VDDCPU") (class "Default")
      (node (ref "C62") (pin "1") (pinfunction "1_1") (pintype "passive"))
      (node (ref "C63") (pin "2") (pinfunction "2_2") (pintype "passive"))
      (node (ref "C64") (pin "2") (pinfunction "2_2") (pintype "passive"))
      (node (ref "C65") (pin "1") (pinfunction "1_1") (pintype "passive"))
      (node (ref "C66") (pin "2") (pinfunction "2_2") (pintype "passive"))
      (node (ref "C67") (pin "2") (pinfunction "2_2") (pintype "passive"))
      (node (ref "C68") (pin "2") (pinfunction "2_2") (pintype "passive"))
      (node (ref "C69") (pin "2") (pinfunction "2_2") (pintype "passive"))
      (node (ref "U1") (pin "1C7") (pinfunction "VDDCPU_1C7") (pintype "passive"))
      (node (ref "U1") (pin "1C9") (pinfunction "VDDCPU_1C9") (pintype "passive"))
      (node (ref "U1") (pin "1D10") (pinfunction "VDDCPU_1D10") (pintype "passive"))
      (node (ref "U1") (pin "1D6") (pinfunction "VDDCPU_1D6") (pintype "passive"))
      (node (ref "U1") (pin "1D8") (pinfunction "VDDCPU_1D8") (pintype "passive"))
      (node (ref "U1") (pin "F18") (pinfunction "VDDCPU_F18") (pintype "passive"))
      (node (ref "U1") (pin "G15") (pinfunction "VDDCPU_G15") (pintype "passive"))
      (node (ref "U1") (pin "G17") (pinfunction "VDDCPU_G17") (pintype "passive"))
    )
    (net (code "16") (name "VDDGPU") (class "Default")
      (node (ref "C52") (pin "2") (pinfunction "2_2") (pintype "passive"))
      (node (ref "C53") (pin "2") (pinfunction "2_2") (pintype "passive"))
      (node (ref "C54") (pin "2") (pinfunction "2_2") (pintype "passive"))
      (node (ref "C55") (pin "2") (pinfunction "2_2") (pintype "passive"))
      (node (ref "C57") (pin "2") (pinfunction "2_2") (pintype "passive"))
      (node (ref "C58") (pin "2") (pinfunction "2_2") (pintype "passive"))
      (node (ref "C59") (pin "2") (pinfunction "2_2") (pintype "passive"))
      (node (ref "C60") (pin "2") (pinfunction "2_2") (pintype "passive"))
      (node (ref "U1") (pin "1G7") (pinfunction "VDDGPU_1G7") (pintype "passive"))
      (node (ref "U1") (pin "1G9") (pinfunction "VDDGPU_1G9") (pintype "passive"))
      (node (ref "U1") (pin "1H10") (pinfunction "VDDGPU_1H10") (pintype "passive"))
      (node (ref "U1") (pin "1H6") (pinfunction "VDDGPU_1H6") (pintype "passive"))
      (node (ref "U1") (pin "1H8") (pinfunction "VDDGPU_1H8") (pintype "passive"))
      (node (ref "U1") (pin "1L7") (pinfunction "VDDGPU_1L7") (pintype "passive"))
      (node (ref "U1") (pin "1L9") (pinfunction "VDDGPU_1L9") (pintype "passive"))
      (node (ref "U1") (pin "1M10") (pinfunction "VDDGPU_1M10") (pintype "passive"))
      (node (ref "U1") (pin "1M6") (pinfunction "VDDGPU_1M6") (pintype "passive"))
      (node (ref "U1") (pin "1M8") (pinfunction "VDDGPU_1M8") (pintype "passive"))
    )
    (net (code "17") (name "VDDIO") (class "Default")
      (node (ref "C196") (pin "2") (pinfunction "2_2") (pintype "passive"))
      (node (ref "C205") (pin "2") (pinfunction "2_2") (pintype "passive"))
      (node (ref "C70") (pin "1") (pinfunction "1_1") (pintype "passive"))
      (node (ref "C71") (pin "2") (pinfunction "2_2") (pintype "passive"))
      (node (ref "C72") (pin "2") (pinfunction "2_2") (pintype "passive"))
      (node (ref "C73") (pin "1") (pinfunction "1_1") (pintype "passive"))
      (node (ref "C74") (pin "2") (pinfunction "2_2") (pintype "passive"))
      (node (ref "R67") (pin "2") (pinfunction "2_2") (pintype "passive"))
      (node (ref "U1") (pin "1L1") (pinfunction "VDD_1L1") (pintype "passive"))
      (node (ref "U1") (pin "1L3") (pinfunction "VDD_1L3") (pintype "passive"))
      (node (ref "U1") (pin "1L5") (pinfunction "VDD_1L5") (pintype "passive"))
      (node (ref "U1") (pin "1M2") (pinfunction "VDD_1M2") (pintype "passive"))
      (node (ref "U1") (pin "1M4") (pinfunction "VDD_1M4") (pintype "passive"))
      (node (ref "U1") (pin "D10") (pinfunction "VDDIO3_D10") (pintype "passive"))
      (node (ref "U1") (pin "E11") (pinfunction "VDDIO3_E11") (pintype "passive"))
      (node (ref "U1") (pin "E9") (pinfunction "VDDIO4_E9") (pintype "passive"))
      (node (ref "U1") (pin "G11") (pinfunction "VDDIO4_G11") (pintype "passive"))
    )
    (net (code "18") (name "VDDIO_SDCARD") (class "Default")
      (node (ref "C195") (pin "2") (pinfunction "2_2") (pintype "passive"))
      (node (ref "U1") (pin "D14") (pinfunction "VDDIO1_D14") (pintype "passive"))
      (node (ref "U1") (pin "E13") (pinfunction "VDDIO1_E13") (pintype "passive"))
    )
    (net (code "19") (name "VREF+") (class "Default")
      (node (ref "C248") (pin "2") (pinfunction "2_2") (pintype "passive"))
      (node (ref "C250") (pin "2") (pinfunction "2_2") (pintype "passive"))
      (node (ref "R269") (pin "2") (pinfunction "2_2") (pintype "passive"))
      (node (ref "U1") (pin "AG6") (pinfunction "VREFP_AG6") (pintype "passive"))
    )
  )
)
